# PushButtons.net
KiCad netlist of a schematic drawn in EAGLE
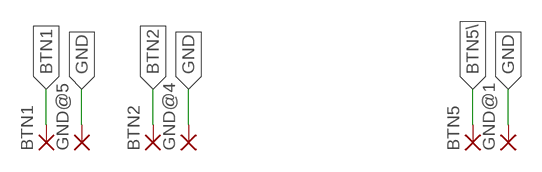
[diagram p0: schematic, sheet 1]

(export (version "E")
  (design (tool "Eeschema 10.0.6"))
  (components
    (comp (ref "BTN1")
      (value "SMD5")
      (footprint "eagle-import:SMD2,54-5,08")
      (libsource (lib "eagle-import") (part "SMD5"))
    )
    (comp (ref "BTN2")
      (value "SMD5")
      (footprint "eagle-import:SMD2,54-5,08")
      (libsource (lib "eagle-import") (part "SMD5"))
    )
    (comp (ref "BTN5")
      (value "SMD5")
      (footprint "eagle-import:SMD2,54-5,08")
      (libsource (lib "eagle-import") (part "SMD5"))
    )
    (comp (ref "GND@1")
      (value "SMD5")
      (footprint "eagle-import:SMD2,54-5,08")
      (libsource (lib "eagle-import") (part "SMD5"))
    )
    (comp (ref "GND@4")
      (value "SMD5")
      (footprint "eagle-import:SMD2,54-5,08")
      (libsource (lib "eagle-import") (part "SMD5"))
    )
    (comp (ref "GND@5")
      (value "SMD5")
      (footprint "eagle-import:SMD2,54-5,08")
      (libsource (lib "eagle-import") (part "SMD5"))
    )
  )
  (nets
    (net (code "1") (name "BTN1") (class "Default")
      (node (ref "BTN1") (pin "1") (pinfunction "P_1") (pintype "passive"))
    )
    (net (code "2") (name "BTN2") (class "Default")
      (node (ref "BTN2") (pin "1") (pinfunction "P_1") (pintype "passive"))
    )
    (net (code "3") (name "BTN5\\") (class "Default")
      (node (ref "BTN5") (pin "1") (pinfunction "P_1") (pintype "passive"))
    )
    (net (code "4") (name "GND") (class "Default")
      (node (ref "GND@1") (pin "1") (pinfunction "P_1") (pintype "passive"))
      (node (ref "GND@4") (pin "1") (pinfunction "P_1") (pintype "passive"))
      (node (ref "GND@5") (pin "1") (pinfunction "P_1") (pintype "passive"))
    )
  )
)
